# em32f103cb_main.net
KiCad netlist of a schematic drawn in Altium Designer
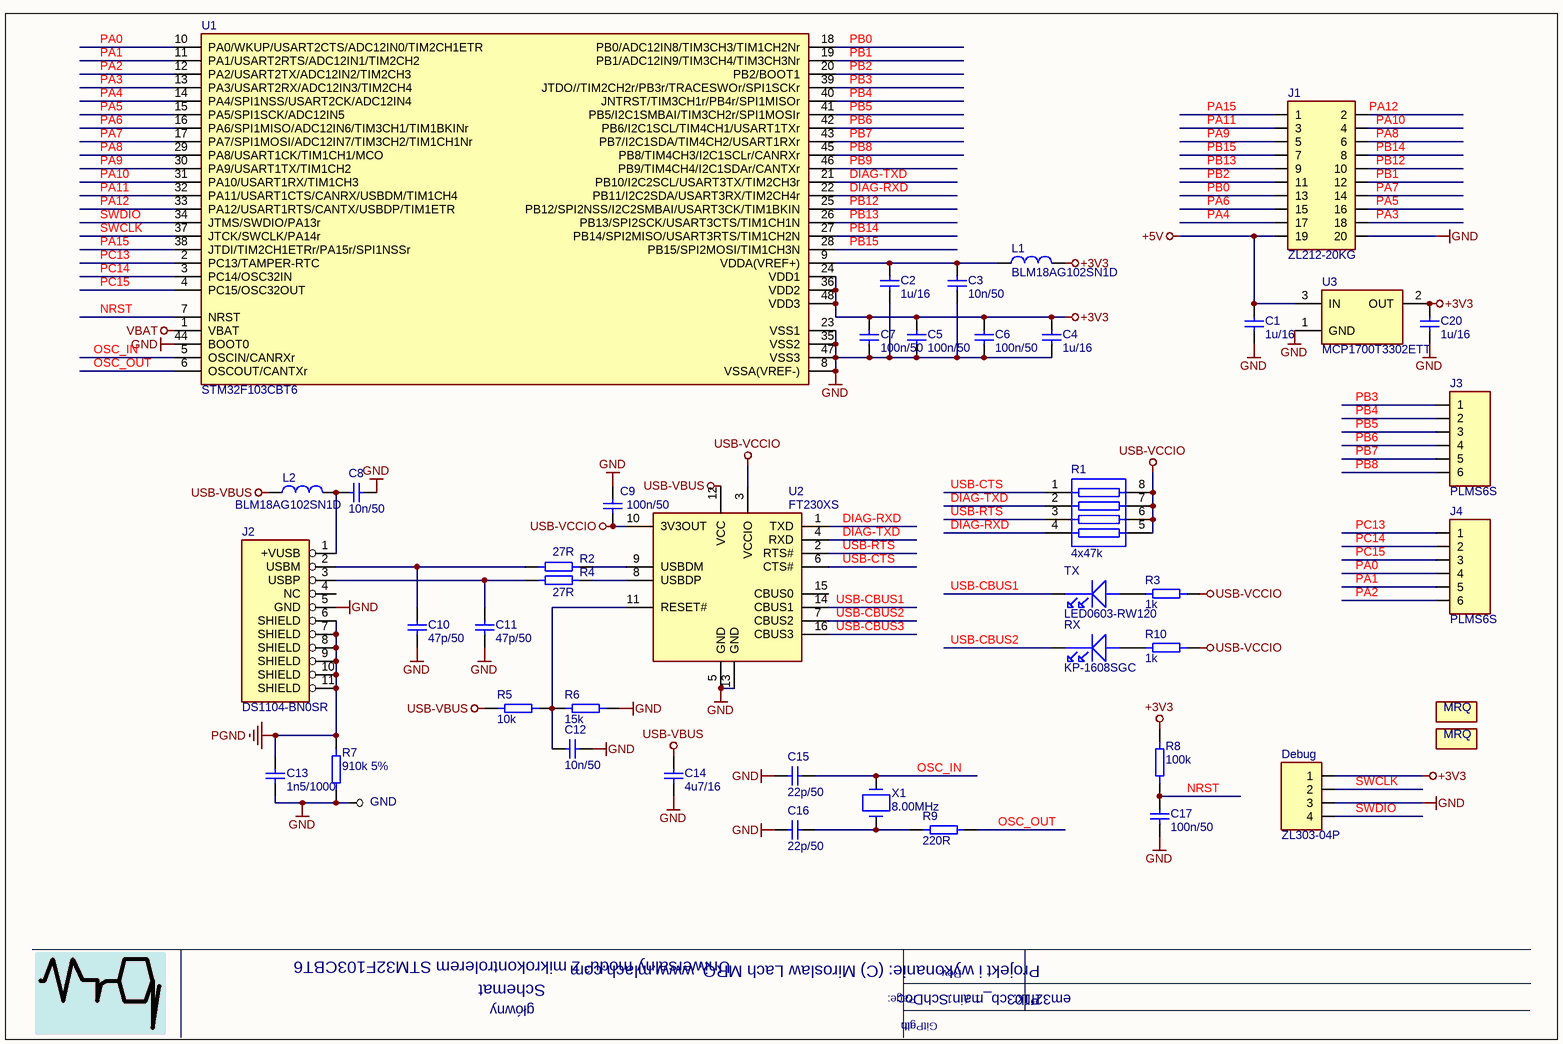
[diagram p0: em32f103cb_main.SchDoc]

(export (version "E")
  (design (tool "Eeschema 10.0.6"))
  (components
    (comp (ref "C1")
      (value "CL10B105KO8NNNC")
      (footprint "0603-IPC")
      (fields (field (name "OTHERPARAMS") "1u/16") (field (name "TOLERANCE") "10%"))
      (libsource (lib "Parts") (part "C"))
    )
    (comp (ref "C2")
      (value "CL10B105KO8NNNC")
      (footprint "0603-IPC")
      (fields (field (name "OTHERPARAMS") "1u/16") (field (name "TOLERANCE") "10%"))
      (libsource (lib "Parts") (part "C"))
    )
    (comp (ref "C3")
      (value "06035C103KAT2A")
      (footprint "0603-IPC")
      (fields (field (name "OTHERPARAMS") "10n/50") (field (name "TOLERANCE") "10%"))
      (libsource (lib "Parts") (part "C"))
    )
    (comp (ref "C4")
      (value "CL10B105KO8NNNC")
      (footprint "0603-IPC")
      (fields (field (name "OTHERPARAMS") "1u/16") (field (name "TOLERANCE") "10%"))
      (libsource (lib "Parts") (part "C"))
    )
    (comp (ref "C5")
      (value "CL10B104JB8NNNC")
      (footprint "0603-IPC")
      (fields (field (name "OTHERPARAMS") "100n/50") (field (name "TOLERANCE") "10%"))
      (libsource (lib "Parts") (part "C"))
    )
    (comp (ref "C6")
      (value "CL10B104JB8NNNC")
      (footprint "0603-IPC")
      (fields (field (name "OTHERPARAMS") "100n/50") (field (name "TOLERANCE") "10%"))
      (libsource (lib "Parts") (part "C"))
    )
    (comp (ref "C7")
      (value "CL10B104JB8NNNC")
      (footprint "0603-IPC")
      (fields (field (name "OTHERPARAMS") "100n/50") (field (name "TOLERANCE") "10%"))
      (libsource (lib "Parts") (part "C"))
    )
    (comp (ref "C8")
      (value "06035C103KAT2A")
      (footprint "0603-IPC")
      (fields (field (name "OTHERPARAMS") "10n/50") (field (name "TOLERANCE") "10%"))
      (libsource (lib "Parts") (part "C"))
    )
    (comp (ref "C9")
      (value "CL10B104JB8NNNC")
      (footprint "0603-IPC")
      (fields (field (name "OTHERPARAMS") "100n/50") (field (name "TOLERANCE") "10%"))
      (libsource (lib "Parts") (part "C"))
    )
    (comp (ref "C10")
      (value "CC0603JRNPO9BN470")
      (footprint "0603-IPC")
      (fields (field (name "OTHERPARAMS") "47p/50") (field (name "TOLERANCE") "5%"))
      (libsource (lib "Parts") (part "C"))
    )
    (comp (ref "C11")
      (value "CC0603JRNPO9BN470")
      (footprint "0603-IPC")
      (fields (field (name "OTHERPARAMS") "47p/50") (field (name "TOLERANCE") "5%"))
      (libsource (lib "Parts") (part "C"))
    )
    (comp (ref "C12")
      (value "06035C103KAT2A")
      (footprint "0603-IPC")
      (fields (field (name "OTHERPARAMS") "10n/50") (field (name "TOLERANCE") "10%"))
      (libsource (lib "Parts") (part "C"))
    )
    (comp (ref "C13")
      (value "MCCA000836")
      (footprint "1210")
      (fields (field (name "OTHERPARAMS") "1n5/1000") (field (name "TOLERANCE") "10%"))
      (libsource (lib "Parts") (part "C"))
    )
    (comp (ref "C14")
      (value "0805YC475KAT2A")
      (footprint "0805")
      (fields (field (name "OTHERPARAMS") "4u7/16") (field (name "TOLERANCE") "10%"))
      (libsource (lib "Parts") (part "C"))
    )
    (comp (ref "C15")
      (value "CL21C220JBANNNC")
      (footprint "0805")
      (fields (field (name "OTHERPARAMS") "22p/50") (field (name "TOLERANCE") "5%"))
      (libsource (lib "Parts") (part "C"))
    )
    (comp (ref "C16")
      (value "CL21C220JBANNNC")
      (footprint "0805")
      (fields (field (name "OTHERPARAMS") "22p/50") (field (name "TOLERANCE") "5%"))
      (libsource (lib "Parts") (part "C"))
    )
    (comp (ref "C17")
      (value "CL10B104JB8NNNC")
      (footprint "0603-IPC")
      (fields (field (name "OTHERPARAMS") "100n/50") (field (name "TOLERANCE") "10%"))
      (libsource (lib "Parts") (part "C"))
    )
    (comp (ref "C20")
      (value "CL10B105KO8NNNC")
      (footprint "0603-IPC")
      (fields (field (name "OTHERPARAMS") "1u/16") (field (name "TOLERANCE") "10%"))
      (libsource (lib "Parts") (part "C"))
    )
    (comp (ref "Debug") (value "ZL303-04P") (footprint "PLMS4S") (libsource (lib "Parts") (part "HEADER4")))
    (comp (ref "GND") (value "LST1506") (footprint "LST1506") (libsource (lib "Parts") (part "PAD4_5MM")))
    (comp (ref "J1") (value "ZL212-20KG") (footprint "PLD20R") (libsource (lib "Parts") (part "HEADER10X2")))
    (comp (ref "J2")
      (value "DS1104-BN0SR")
      (footprint "USBMS1B5")
      (libsource (lib "Parts") (part "USBMS1B5"))
    )
    (comp (ref "J3") (value "PLMS6S") (footprint "PLMS6S") (libsource (lib "Parts") (part "HEADER6")))
    (comp (ref "J4") (value "PLMS6S") (footprint "PLMS6S") (libsource (lib "Parts") (part "HEADER6")))
    (comp (ref "L1")
      (value "BLM18AG102SN1D")
      (footprint "0603-IPC")
      (fields (field (name "OTHERPARAMS") "BLM18AG102SN1D"))
      (libsource (lib "Parts") (part "INDUCTOR"))
    )
    (comp (ref "L2")
      (value "BLM18AG102SN1D")
      (footprint "0603-IPC")
      (fields (field (name "OTHERPARAMS") "BLM18AG102SN1D"))
      (libsource (lib "") (part "INDUCTOR_1"))
    )
    (comp (ref "LOGO1") (value "MRQ_1_8") (footprint "MRQ_1_8") (libsource (lib "Parts") (part "MRQLOGO")))
    (comp (ref "LOGO2") (value "MRQ_1_8") (footprint "MRQ_1_8") (libsource (lib "Parts") (part "MRQLOGO")))
    (comp (ref "R1")
      (value "4x47k")
      (footprint "1206RP")
      (fields (field (name "TOLERANCE") "5%"))
      (libsource (lib "Parts") (part "DR1206"))
    )
    (comp (ref "R2")
      (value "0603SAF270JT5E")
      (footprint "0603-IPC")
      (fields (field (name "OTHERPARAMS") "27R") (field (name "TOLERANCE") "1%"))
      (libsource (lib "Parts") (part "R"))
    )
    (comp (ref "R3")
      (value "0603SAF1001T5E")
      (footprint "0603-IPC")
      (fields (field (name "OTHERPARAMS") "1k") (field (name "TOLERANCE") "1%"))
      (libsource (lib "Parts") (part "R"))
    )
    (comp (ref "R4")
      (value "0603SAF270JT5E")
      (footprint "0603-IPC")
      (fields (field (name "OTHERPARAMS") "27R") (field (name "TOLERANCE") "1%"))
      (libsource (lib "Parts") (part "R"))
    )
    (comp (ref "R5")
      (value "0603WGF10KT5E")
      (footprint "0603-IPC")
      (fields (field (name "OTHERPARAMS") "10k") (field (name "TOLERANCE") "1%"))
      (libsource (lib "Parts") (part "R"))
    )
    (comp (ref "R6")
      (value "0603WGF15KT5E")
      (footprint "0603-IPC")
      (fields (field (name "OTHERPARAMS") "15k") (field (name "TOLERANCE") "1%"))
      (libsource (lib "Parts") (part "R"))
    )
    (comp (ref "R7")
      (value "25121WJ 910K T5E")
      (footprint "2512")
      (fields (field (name "OTHERPARAMS") "910k 5%") (field (name "TOLERANCE") "5%"))
      (libsource (lib "Parts") (part "R"))
    )
    (comp (ref "R8")
      (value "0805WAF 100K T5E")
      (footprint "0805")
      (fields (field (name "OTHERPARAMS") "100k") (field (name "TOLERANCE") "1%"))
      (libsource (lib "Parts") (part "R"))
    )
    (comp (ref "R9")
      (value "0805WAF 220R T5E")
      (footprint "0805")
      (fields (field (name "OTHERPARAMS") "220R") (field (name "TOLERANCE") "1%"))
      (libsource (lib "Parts") (part "R"))
    )
    (comp (ref "R10")
      (value "0603SAF1001T5E")
      (footprint "0603-IPC")
      (fields (field (name "OTHERPARAMS") "1k") (field (name "TOLERANCE") "1%"))
      (libsource (lib "Parts") (part "R"))
    )
    (comp (ref "RX") (value "KP-1608SGC") (footprint "D0603") (libsource (lib "Parts") (part "LED")))
    (comp (ref "TX") (value "LED0603-RW120") (footprint "D0603") (libsource (lib "Parts") (part "LED")))
    (comp (ref "U1")
      (value "STM32F103CBT6")
      (footprint "MS-026ABC")
      (libsource (lib "Parts") (part "STM32F103CBT6"))
    )
    (comp (ref "U2") (value "FT230XS") (footprint "MO-137AB") (libsource (lib "Parts") (part "FT230XS")))
    (comp (ref "U3")
      (value "MCP1700T3302ETT")
      (footprint "SOT23-3")
      (libsource (lib "Parts") (part "MCP1700"))
    )
    (comp (ref "X1") (value "8.00MHz") (footprint "HC49SMP") (libsource (lib "Parts") (part "CRYSTAL")))
  )
  (nets
    (net (code "1") (name "+3V3") (class "Default")
      (node (ref "C20") (pin "1") (pinfunction "1_1") (pintype "passive"))
      (node (ref "C4") (pin "1") (pinfunction "1_1") (pintype "passive"))
      (node (ref "C5") (pin "1") (pinfunction "1_1") (pintype "passive"))
      (node (ref "C6") (pin "1") (pinfunction "1_1") (pintype "passive"))
      (node (ref "C7") (pin "1") (pinfunction "1_1") (pintype "passive"))
      (node (ref "Debug") (pin "1") (pinfunction "1_1") (pintype "passive"))
      (node (ref "L1") (pin "2") (pinfunction "2_2") (pintype "passive"))
      (node (ref "R8") (pin "1") (pinfunction "1_1") (pintype "passive"))
      (node (ref "U1") (pin "24") (pinfunction "VDD1_24") (pintype "passive"))
      (node (ref "U1") (pin "36") (pinfunction "VDD2_36") (pintype "passive"))
      (node (ref "U1") (pin "48") (pinfunction "VDD3_48") (pintype "passive"))
      (node (ref "U3") (pin "2") (pinfunction "OUT_2") (pintype "passive"))
    )
    (net (code "2") (name "+5V") (class "Default")
      (node (ref "C1") (pin "1") (pinfunction "1_1") (pintype "passive"))
      (node (ref "J1") (pin "19") (pinfunction "19_19") (pintype "passive"))
      (node (ref "U3") (pin "3") (pinfunction "IN_3") (pintype "passive"))
    )
    (net (code "3") (name "/DIAG-RXD") (class "Default")
      (node (ref "R1") (pin "4") (pinfunction "R4_4") (pintype "passive"))
      (node (ref "U1") (pin "22") (pinfunction "PB11/I2C2SDA/USART3RX/TIM2CH4r_22") (pintype "passive"))
      (node (ref "U2") (pin "1") (pinfunction "TXD_1") (pintype "passive"))
    )
    (net (code "4") (name "/DIAG-TXD") (class "Default")
      (node (ref "R1") (pin "2") (pinfunction "R2_2") (pintype "passive"))
      (node (ref "U1") (pin "21") (pinfunction "PB10/I2C2SCL/USART3TX/TIM2CH3r_21") (pintype "passive"))
      (node (ref "U2") (pin "4") (pinfunction "RXD_4") (pintype "passive"))
    )
    (net (code "5") (name "/NRST") (class "Default")
      (node (ref "C17") (pin "1") (pinfunction "1_1") (pintype "passive"))
      (node (ref "R8") (pin "2") (pinfunction "2_2") (pintype "passive"))
      (node (ref "U1") (pin "7") (pinfunction "NRST_7") (pintype "passive"))
    )
    (net (code "6") (name "/OSC_IN") (class "Default")
      (node (ref "C15") (pin "2") (pinfunction "2_2") (pintype "passive"))
      (node (ref "U1") (pin "5") (pinfunction "OSCIN/CANRXr_5") (pintype "passive"))
      (node (ref "X1") (pin "1") (pinfunction "1_1") (pintype "passive"))
    )
    (net (code "7") (name "/OSC_OUT") (class "Default")
      (node (ref "R9") (pin "2") (pinfunction "2_2") (pintype "passive"))
      (node (ref "U1") (pin "6") (pinfunction "OSCOUT/CANTXr_6") (pintype "passive"))
    )
    (net (code "8") (name "/PA0") (class "Default")
      (node (ref "J4") (pin "4") (pinfunction "4_4") (pintype "passive"))
      (node (ref "U1") (pin "10") (pinfunction "PA0/WKUP/USART2CTS/ADC12IN0/TIM2CH1ETR_10") (pintype "passive"))
    )
    (net (code "9") (name "/PA1") (class "Default")
      (node (ref "J4") (pin "5") (pinfunction "5_5") (pintype "passive"))
      (node (ref "U1") (pin "11") (pinfunction "PA1/USART2RTS/ADC12IN1/TIM2CH2_11") (pintype "passive"))
    )
    (net (code "10") (name "/PA2") (class "Default")
      (node (ref "J4") (pin "6") (pinfunction "6_6") (pintype "passive"))
      (node (ref "U1") (pin "12") (pinfunction "PA2/USART2TX/ADC12IN2/TIM2CH3_12") (pintype "passive"))
    )
    (net (code "11") (name "/PA3") (class "Default")
      (node (ref "J1") (pin "18") (pinfunction "18_18") (pintype "passive"))
      (node (ref "U1") (pin "13") (pinfunction "PA3/USART2RX/ADC12IN3/TIM2CH4_13") (pintype "passive"))
    )
    (net (code "12") (name "/PA4") (class "Default")
      (node (ref "J1") (pin "17") (pinfunction "17_17") (pintype "passive"))
      (node (ref "U1") (pin "14") (pinfunction "PA4/SPI1NSS/USART2CK/ADC12IN4_14") (pintype "passive"))
    )
    (net (code "13") (name "/PA5") (class "Default")
      (node (ref "J1") (pin "16") (pinfunction "16_16") (pintype "passive"))
      (node (ref "U1") (pin "15") (pinfunction "PA5/SPI1SCK/ADC12IN5_15") (pintype "passive"))
    )
    (net (code "14") (name "/PA6") (class "Default")
      (node (ref "J1") (pin "15") (pinfunction "15_15") (pintype "passive"))
      (node (ref "U1") (pin "16") (pinfunction "PA6/SPI1MISO/ADC12IN6/TIM3CH1/TIM1BKINr_16") (pintype "passive"))
    )
    (net (code "15") (name "/PA7") (class "Default")
      (node (ref "J1") (pin "14") (pinfunction "14_14") (pintype "passive"))
      (node (ref "U1") (pin "17") (pinfunction "PA7/SPI1MOSI/ADC12IN7/TIM3CH2/TIM1CH1Nr_17") (pintype "passive"))
    )
    (net (code "16") (name "/PA8") (class "Default")
      (node (ref "J1") (pin "6") (pinfunction "6_6") (pintype "passive"))
      (node (ref "U1") (pin "29") (pinfunction "PA8/USART1CK/TIM1CH1/MCO_29") (pintype "passive"))
    )
    (net (code "17") (name "/PA9") (class "Default")
      (node (ref "J1") (pin "5") (pinfunction "5_5") (pintype "passive"))
      (node (ref "U1") (pin "30") (pinfunction "PA9/USART1TX/TIM1CH2_30") (pintype "passive"))
    )
    (net (code "18") (name "/PA10") (class "Default")
      (node (ref "J1") (pin "4") (pinfunction "4_4") (pintype "passive"))
      (node (ref "U1") (pin "31") (pinfunction "PA10/USART1RX/TIM1CH3_31") (pintype "passive"))
    )
    (net (code "19") (name "/PA11") (class "Default")
      (node (ref "J1") (pin "3") (pinfunction "3_3") (pintype "passive"))
      (node (ref "U1") (pin "32") (pinfunction "PA11/USART1CTS/CANRX/USBDM/TIM1CH4_32") (pintype "passive"))
    )
    (net (code "20") (name "/PA12") (class "Default")
      (node (ref "J1") (pin "2") (pinfunction "2_2") (pintype "passive"))
      (node (ref "U1") (pin "33") (pinfunction "PA12/USART1RTS/CANTX/USBDP/TIM1ETR_33") (pintype "passive"))
    )
    (net (code "21") (name "/PA15") (class "Default")
      (node (ref "J1") (pin "1") (pinfunction "1_1") (pintype "passive"))
      (node (ref "U1") (pin "38") (pinfunction "JTDI/TIM2CH1ETRr/PA15r/SPI1NSSr_38") (pintype "passive"))
    )
    (net (code "22") (name "/PB0") (class "Default")
      (node (ref "J1") (pin "13") (pinfunction "13_13") (pintype "passive"))
      (node (ref "U1") (pin "18") (pinfunction "PB0/ADC12IN8/TIM3CH3/TIM1CH2Nr_18") (pintype "passive"))
    )
    (net (code "23") (name "/PB1") (class "Default")
      (node (ref "J1") (pin "12") (pinfunction "12_12") (pintype "passive"))
      (node (ref "U1") (pin "19") (pinfunction "PB1/ADC12IN9/TIM3CH4/TIM3CH3Nr_19") (pintype "passive"))
    )
    (net (code "24") (name "/PB2") (class "Default")
      (node (ref "J1") (pin "11") (pinfunction "11_11") (pintype "passive"))
      (node (ref "U1") (pin "20") (pinfunction "PB2/BOOT1_20") (pintype "passive"))
    )
    (net (code "25") (name "/PB3") (class "Default")
      (node (ref "J3") (pin "1") (pinfunction "1_1") (pintype "passive"))
      (node (ref "U1") (pin "39") (pinfunction "JTDO//TIM2CH2r/PB3r/TRACESWOr/SPI1SCKr_39") (pintype "passive"))
    )
    (net (code "26") (name "/PB4") (class "Default")
      (node (ref "J3") (pin "2") (pinfunction "2_2") (pintype "passive"))
      (node (ref "U1") (pin "40") (pinfunction "JNTRST/TIM3CH1r/PB4r/SPI1MISOr_40") (pintype "passive"))
    )
    (net (code "27") (name "/PB5") (class "Default")
      (node (ref "J3") (pin "3") (pinfunction "3_3") (pintype "passive"))
      (node (ref "U1") (pin "41") (pinfunction "PB5/I2C1SMBAI/TIM3CH2r/SPI1MOSIr_41") (pintype "passive"))
    )
    (net (code "28") (name "/PB6") (class "Default")
      (node (ref "J3") (pin "4") (pinfunction "4_4") (pintype "passive"))
      (node (ref "U1") (pin "42") (pinfunction "PB6/I2C1SCL/TIM4CH1/USART1TXr_42") (pintype "passive"))
    )
    (net (code "29") (name "/PB7") (class "Default")
      (node (ref "J3") (pin "5") (pinfunction "5_5") (pintype "passive"))
      (node (ref "U1") (pin "43") (pinfunction "PB7/I2C1SDA/TIM4CH2/USART1RXr_43") (pintype "passive"))
    )
    (net (code "30") (name "/PB8") (class "Default")
      (node (ref "J3") (pin "6") (pinfunction "6_6") (pintype "passive"))
      (node (ref "U1") (pin "45") (pinfunction "PB8/TIM4CH3/I2C1SCLr/CANRXr_45") (pintype "passive"))
    )
    (net (code "31") (name "/PB9") (class "Default")
      (node (ref "U1") (pin "46") (pinfunction "PB9/TIM4CH4/I2C1SDAr/CANTXr_46") (pintype "passive"))
    )
    (net (code "32") (name "/PB12") (class "Default")
      (node (ref "J1") (pin "10") (pinfunction "10_10") (pintype "passive"))
      (node (ref "U1") (pin "25") (pinfunction "PB12/SPI2NSS/I2C2SMBAI/USART3CK/TIM1BKIN_25") (pintype "passive"))
    )
    (net (code "33") (name "/PB13") (class "Default")
      (node (ref "J1") (pin "9") (pinfunction "9_9") (pintype "passive"))
      (node (ref "U1") (pin "26") (pinfunction "PB13/SPI2SCK/USART3CTS/TIM1CH1N_26") (pintype "passive"))
    )
    (net (code "34") (name "/PB14") (class "Default")
      (node (ref "J1") (pin "8") (pinfunction "8_8") (pintype "passive"))
      (node (ref "U1") (pin "27") (pinfunction "PB14/SPI2MISO/USART3RTS/TIM1CH2N_27") (pintype "passive"))
    )
    (net (code "35") (name "/PB15") (class "Default")
      (node (ref "J1") (pin "7") (pinfunction "7_7") (pintype "passive"))
      (node (ref "U1") (pin "28") (pinfunction "PB15/SPI2MOSI/TIM1CH3N_28") (pintype "passive"))
    )
    (net (code "36") (name "/PC13") (class "Default")
      (node (ref "J4") (pin "1") (pinfunction "1_1") (pintype "passive"))
      (node (ref "U1") (pin "2") (pinfunction "PC13/TAMPER-RTC_2") (pintype "passive"))
    )
    (net (code "37") (name "/PC14") (class "Default")
      (node (ref "J4") (pin "2") (pinfunction "2_2") (pintype "passive"))
      (node (ref "U1") (pin "3") (pinfunction "PC14/OSC32IN_3") (pintype "passive"))
    )
    (net (code "38") (name "/PC15") (class "Default")
      (node (ref "J4") (pin "3") (pinfunction "3_3") (pintype "passive"))
      (node (ref "U1") (pin "4") (pinfunction "PC15/OSC32OUT_4") (pintype "passive"))
    )
    (net (code "39") (name "/SWCLK") (class "Default")
      (node (ref "Debug") (pin "2") (pinfunction "2_2") (pintype "passive"))
      (node (ref "U1") (pin "37") (pinfunction "JTCK/SWCLK/PA14r_37") (pintype "passive"))
    )
    (net (code "40") (name "/SWDIO") (class "Default")
      (node (ref "Debug") (pin "4") (pinfunction "4_4") (pintype "passive"))
      (node (ref "U1") (pin "34") (pinfunction "JTMS/SWDIO/PA13r_34") (pintype "passive"))
    )
    (net (code "41") (name "/USB-CBUS1") (class "Default")
      (node (ref "TX") (pin "CATH") (pinfunction "CATH_CATH") (pintype "passive"))
      (node (ref "U2") (pin "14") (pinfunction "CBUS1_14") (pintype "passive"))
    )
    (net (code "42") (name "/USB-CBUS2") (class "Default")
      (node (ref "RX") (pin "CATH") (pinfunction "CATH_CATH") (pintype "passive"))
      (node (ref "U2") (pin "7") (pinfunction "CBUS2_7") (pintype "passive"))
    )
    (net (code "43") (name "/USB-CBUS3") (class "Default")
      (node (ref "U2") (pin "16") (pinfunction "CBUS3_16") (pintype "passive"))
    )
    (net (code "44") (name "/USB-CTS") (class "Default")
      (node (ref "R1") (pin "1") (pinfunction "R1_1") (pintype "passive"))
      (node (ref "U2") (pin "6") (pinfunction "CTS#_6") (pintype "passive"))
    )
    (net (code "45") (name "/USB-RTS") (class "Default")
      (node (ref "R1") (pin "3") (pinfunction "R3_3") (pintype "passive"))
      (node (ref "U2") (pin "2") (pinfunction "RTS#_2") (pintype "passive"))
    )
    (net (code "46") (name "GND") (class "Default")
      (node (ref "C1") (pin "2") (pinfunction "2_2") (pintype "passive"))
      (node (ref "C10") (pin "2") (pinfunction "2_2") (pintype "passive"))
      (node (ref "C11") (pin "2") (pinfunction "2_2") (pintype "passive"))
      (node (ref "C12") (pin "1") (pinfunction "1_1") (pintype "passive"))
      (node (ref "C13") (pin "2") (pinfunction "2_2") (pintype "passive"))
      (node (ref "C14") (pin "2") (pinfunction "2_2") (pintype "passive"))
      (node (ref "C15") (pin "1") (pinfunction "1_1") (pintype "passive"))
      (node (ref "C16") (pin "1") (pinfunction "1_1") (pintype "passive"))
      (node (ref "C17") (pin "2") (pinfunction "2_2") (pintype "passive"))
      (node (ref "C2") (pin "2") (pinfunction "2_2") (pintype "passive"))
      (node (ref "C20") (pin "2") (pinfunction "2_2") (pintype "passive"))
      (node (ref "C3") (pin "2") (pinfunction "2_2") (pintype "passive"))
      (node (ref "C4") (pin "2") (pinfunction "2_2") (pintype "passive"))
      (node (ref "C5") (pin "2") (pinfunction "2_2") (pintype "passive"))
      (node (ref "C6") (pin "2") (pinfunction "2_2") (pintype "passive"))
      (node (ref "C7") (pin "2") (pinfunction "2_2") (pintype "passive"))
      (node (ref "C8") (pin "1") (pinfunction "1_1") (pintype "passive"))
      (node (ref "C9") (pin "1") (pinfunction "1_1") (pintype "passive"))
      (node (ref "Debug") (pin "3") (pinfunction "3_3") (pintype "passive"))
      (node (ref "GND") (pin "1") (pinfunction "1_1") (pintype "passive"))
      (node (ref "J1") (pin "20") (pinfunction "20_20") (pintype "passive"))
      (node (ref "J2") (pin "5") (pinfunction "GND_5") (pintype "passive"))
      (node (ref "R6") (pin "2") (pinfunction "2_2") (pintype "passive"))
      (node (ref "R7") (pin "2") (pinfunction "2_2") (pintype "passive"))
      (node (ref "U1") (pin "23") (pinfunction "VSS1_23") (pintype "passive"))
      (node (ref "U1") (pin "35") (pinfunction "VSS2_35") (pintype "passive"))
      (node (ref "U1") (pin "44") (pinfunction "BOOT0_44") (pintype "passive"))
      (node (ref "U1") (pin "47") (pinfunction "VSS3_47") (pintype "passive"))
      (node (ref "U1") (pin "8") (pinfunction "VSSA(VREF-)_8") (pintype "passive"))
      (node (ref "U2") (pin "13") (pinfunction "GND_13") (pintype "passive"))
      (node (ref "U2") (pin "5") (pinfunction "GND_5") (pintype "passive"))
      (node (ref "U3") (pin "1") (pinfunction "GND_1") (pintype "passive"))
    )
    (net (code "47") (name "Net-(C16-Pad2)") (class "Default")
      (node (ref "C16") (pin "2") (pinfunction "2_2") (pintype "passive"))
      (node (ref "R9") (pin "1") (pinfunction "1_1") (pintype "passive"))
      (node (ref "X1") (pin "2") (pinfunction "2_2") (pintype "passive"))
    )
    (net (code "48") (name "Net-(J2-+VUSB)") (class "Default")
      (node (ref "C8") (pin "2") (pinfunction "2_2") (pintype "passive"))
      (node (ref "J2") (pin "1") (pinfunction "+VUSB_1") (pintype "passive"))
      (node (ref "L2") (pin "1") (pinfunction "1_1") (pintype "passive"))
    )
    (net (code "49") (name "Net-(J2-USBM)") (class "Default")
      (node (ref "C10") (pin "1") (pinfunction "1_1") (pintype "passive"))
      (node (ref "J2") (pin "2") (pinfunction "USBM_2") (pintype "passive"))
      (node (ref "R2") (pin "1") (pinfunction "1_1") (pintype "passive"))
    )
    (net (code "50") (name "Net-(J2-USBP)") (class "Default")
      (node (ref "C11") (pin "1") (pinfunction "1_1") (pintype "passive"))
      (node (ref "J2") (pin "3") (pinfunction "USBP_3") (pintype "passive"))
      (node (ref "R4") (pin "1") (pinfunction "1_1") (pintype "passive"))
    )
    (net (code "51") (name "Net-(R3-Pad1)") (class "Default")
      (node (ref "R3") (pin "1") (pinfunction "1_1") (pintype "passive"))
      (node (ref "TX") (pin "ANOD") (pinfunction "ANOD_ANOD") (pintype "passive"))
    )
    (net (code "52") (name "Net-(R10-Pad1)") (class "Default")
      (node (ref "R10") (pin "1") (pinfunction "1_1") (pintype "passive"))
      (node (ref "RX") (pin "ANOD") (pinfunction "ANOD_ANOD") (pintype "passive"))
    )
    (net (code "53") (name "Net-(U1-VDDA(VREF+))") (class "Default")
      (node (ref "C2") (pin "1") (pinfunction "1_1") (pintype "passive"))
      (node (ref "C3") (pin "1") (pinfunction "1_1") (pintype "passive"))
      (node (ref "L1") (pin "1") (pinfunction "1_1") (pintype "passive"))
      (node (ref "U1") (pin "9") (pinfunction "VDDA(VREF+)_9") (pintype "passive"))
    )
    (net (code "54") (name "Net-(U2-RESET#)") (class "Default")
      (node (ref "C12") (pin "2") (pinfunction "2_2") (pintype "passive"))
      (node (ref "R5") (pin "2") (pinfunction "2_2") (pintype "passive"))
      (node (ref "R6") (pin "1") (pinfunction "1_1") (pintype "passive"))
      (node (ref "U2") (pin "11") (pinfunction "RESET#_11") (pintype "passive"))
    )
    (net (code "55") (name "Net-(U2-USBDM)") (class "Default")
      (node (ref "R2") (pin "2") (pinfunction "2_2") (pintype "passive"))
      (node (ref "U2") (pin "9") (pinfunction "USBDM_9") (pintype "passive"))
    )
    (net (code "56") (name "Net-(U2-USBDP)") (class "Default")
      (node (ref "R4") (pin "2") (pinfunction "2_2") (pintype "passive"))
      (node (ref "U2") (pin "8") (pinfunction "USBDP_8") (pintype "passive"))
    )
    (net (code "57") (name "PGND") (class "Default")
      (node (ref "C13") (pin "1") (pinfunction "1_1") (pintype "passive"))
      (node (ref "J2") (pin "10") (pinfunction "SHIELD_10") (pintype "passive"))
      (node (ref "J2") (pin "11") (pinfunction "SHIELD_11") (pintype "passive"))
      (node (ref "J2") (pin "6") (pinfunction "SHIELD_6") (pintype "passive"))
      (node (ref "J2") (pin "7") (pinfunction "SHIELD_7") (pintype "passive"))
      (node (ref "J2") (pin "8") (pinfunction "SHIELD_8") (pintype "passive"))
      (node (ref "J2") (pin "9") (pinfunction "SHIELD_9") (pintype "passive"))
      (node (ref "R7") (pin "1") (pinfunction "1_1") (pintype "passive"))
    )
    (net (code "58") (name "USB-VBUS") (class "Default")
      (node (ref "C14") (pin "1") (pinfunction "1_1") (pintype "passive"))
      (node (ref "L2") (pin "2") (pinfunction "2_2") (pintype "passive"))
      (node (ref "R5") (pin "1") (pinfunction "1_1") (pintype "passive"))
      (node (ref "U2") (pin "12") (pinfunction "VCC_12") (pintype "passive"))
    )
    (net (code "59") (name "USB-VCCIO") (class "Default")
      (node (ref "C9") (pin "2") (pinfunction "2_2") (pintype "passive"))
      (node (ref "R1") (pin "5") (pinfunction "R5_5") (pintype "passive"))
      (node (ref "R1") (pin "6") (pinfunction "R6_6") (pintype "passive"))
      (node (ref "R1") (pin "7") (pinfunction "R7_7") (pintype "passive"))
      (node (ref "R1") (pin "8") (pinfunction "R8_8") (pintype "passive"))
      (node (ref "R10") (pin "2") (pinfunction "2_2") (pintype "passive"))
      (node (ref "R3") (pin "2") (pinfunction "2_2") (pintype "passive"))
      (node (ref "U2") (pin "10") (pinfunction "3V3OUT_10") (pintype "passive"))
      (node (ref "U2") (pin "3") (pinfunction "VCCIO_3") (pintype "passive"))
    )
    (net (code "60") (name "VBAT") (class "Default")
      (node (ref "U1") (pin "1") (pinfunction "VBAT_1") (pintype "passive"))
    )
    (net (code "61") (name "unconnected-(J2-NC-Pad4)") (class "Default")
      (node (ref "J2") (pin "4") (pinfunction "NC_4") (pintype "passive"))
    )
    (net (code "62") (name "unconnected-(U2-CBUS0-Pad15)") (class "Default")
      (node (ref "U2") (pin "15") (pinfunction "CBUS0_15") (pintype "passive"))
    )
  )
)
